# RATT_REV0.net
KiCad netlist of a schematic drawn in EAGLE
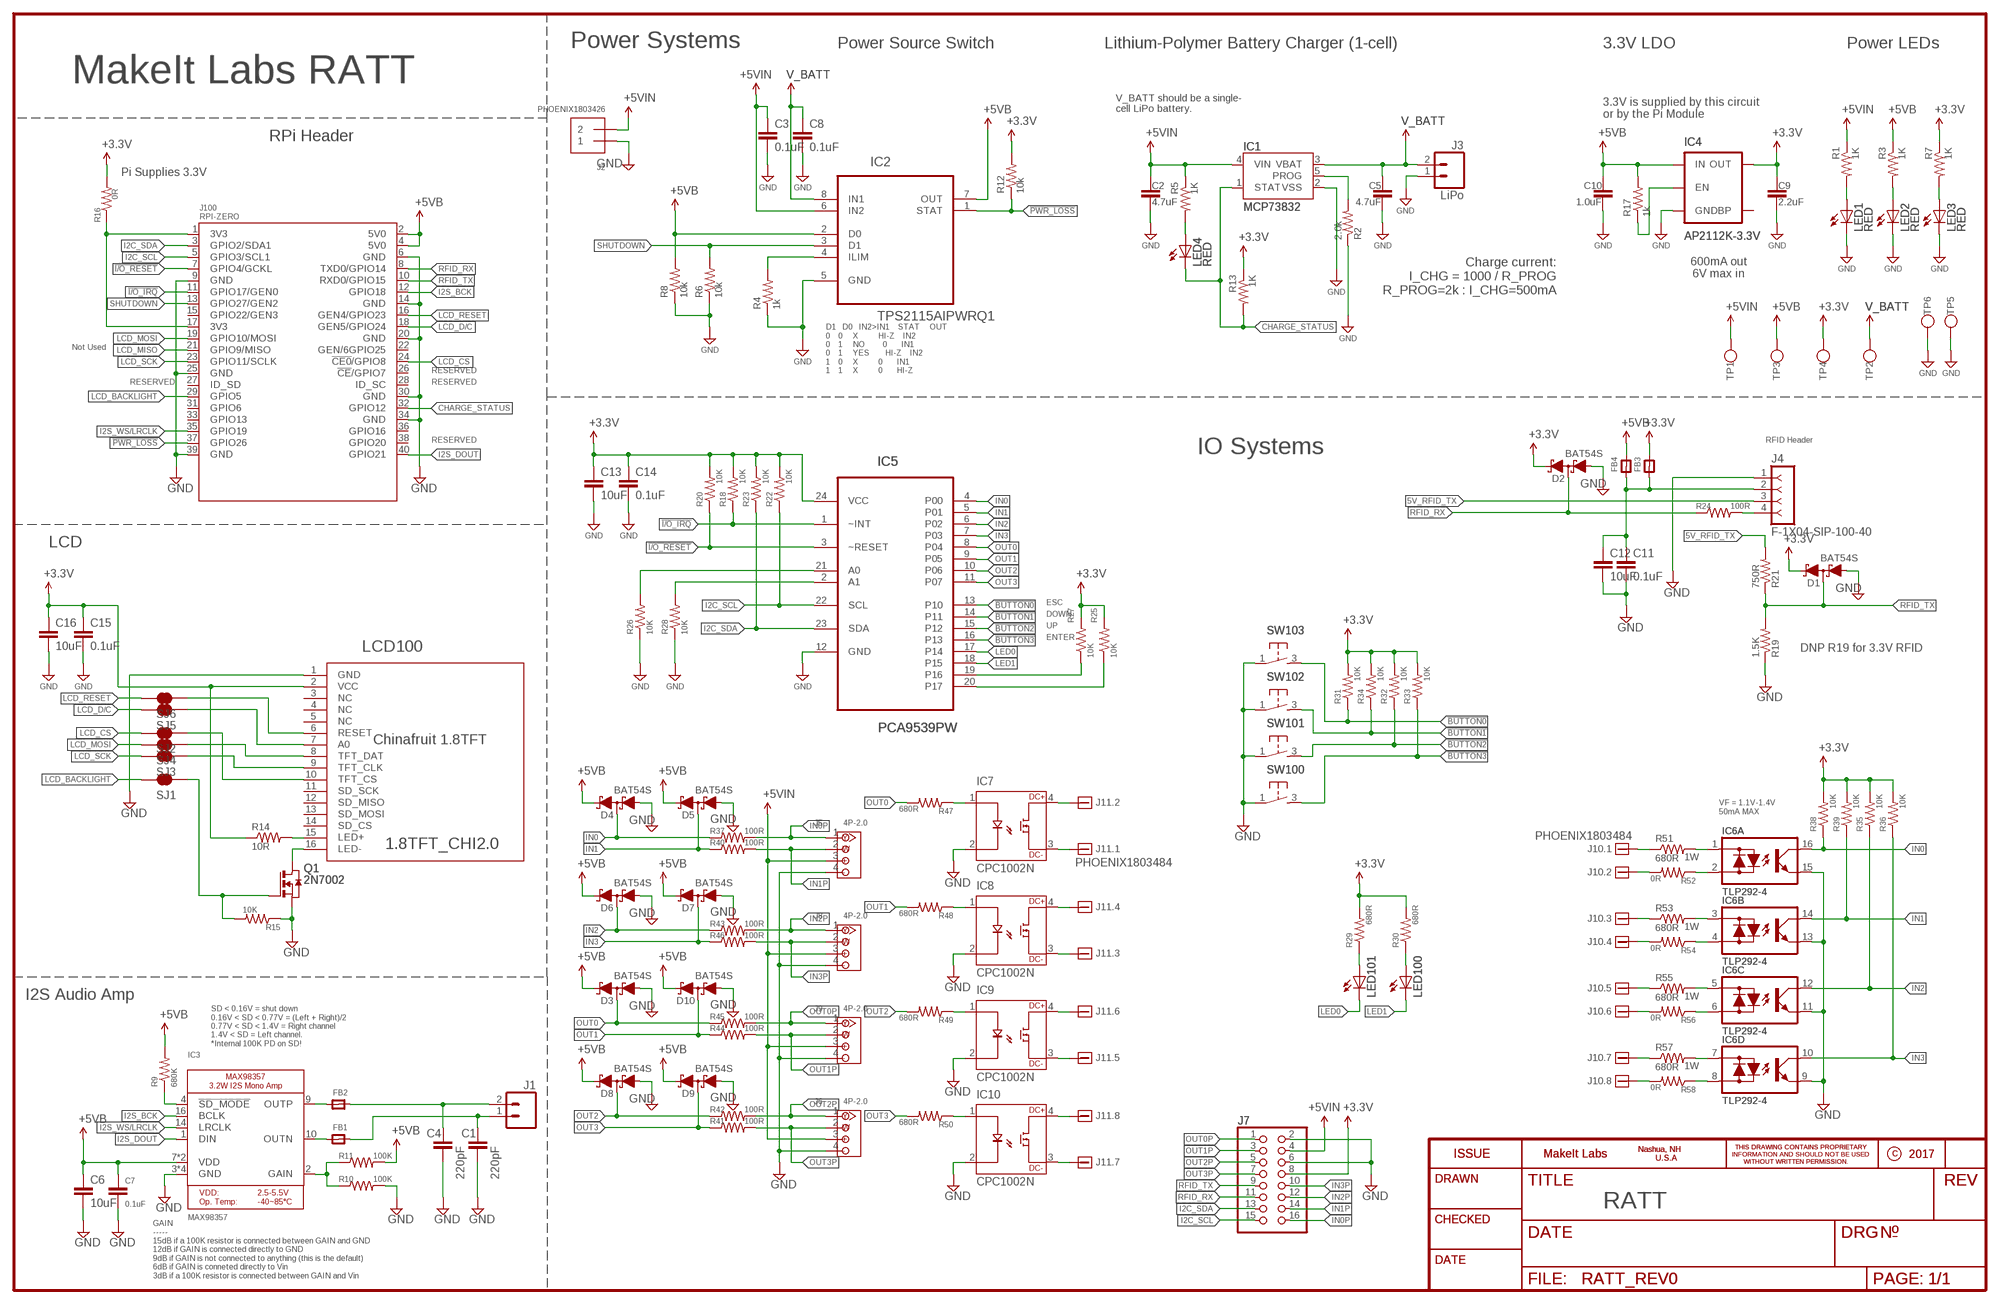
[diagram p0: schematic, sheet 1]

(export (version "E")
  (design (tool "Eeschema 10.0.6"))
  (components
    (comp (ref "C1")
      (value "220pF")
      (footprint "eagle-import:0603-CAP")
      (libsource (lib "eagle-import") (part "CAP0603"))
    )
    (comp (ref "C2")
      (value "4.7uF")
      (footprint "eagle-import:0603-CAP")
      (libsource (lib "eagle-import") (part "CAP0603"))
    )
    (comp (ref "C3")
      (value "0.1uF")
      (footprint "eagle-import:0603-CAP")
      (libsource (lib "eagle-import") (part "CAP0603"))
    )
    (comp (ref "C4")
      (value "220pF")
      (footprint "eagle-import:0603-CAP")
      (libsource (lib "eagle-import") (part "CAP0603"))
    )
    (comp (ref "C5")
      (value "4.7uF")
      (footprint "eagle-import:0603-CAP")
      (libsource (lib "eagle-import") (part "CAP0603"))
    )
    (comp (ref "C6")
      (value "10uF")
      (footprint "eagle-import:0805-CAP")
      (libsource (lib "eagle-import") (part "CAP0805"))
    )
    (comp (ref "C7")
      (value "0.1uF")
      (footprint "eagle-import:0603-CAP")
      (libsource (lib "eagle-import") (part "CAP0603"))
    )
    (comp (ref "C8")
      (value "0.1uF")
      (footprint "eagle-import:0603-CAP")
      (libsource (lib "eagle-import") (part "CAP0603"))
    )
    (comp (ref "C9")
      (value "2.2uF")
      (footprint "eagle-import:0603-CAP")
      (libsource (lib "eagle-import") (part "CAP0603"))
    )
    (comp (ref "C10")
      (value "1.0uF")
      (footprint "eagle-import:0603-CAP")
      (libsource (lib "eagle-import") (part "CAP0603"))
    )
    (comp (ref "C11")
      (value "0.1uF")
      (footprint "eagle-import:0603-CAP")
      (libsource (lib "eagle-import") (part "CAP0603"))
    )
    (comp (ref "C12")
      (value "10uF")
      (footprint "eagle-import:0805-CAP")
      (libsource (lib "eagle-import") (part "CAP0805"))
    )
    (comp (ref "C13")
      (value "10uF")
      (footprint "eagle-import:0805-CAP")
      (libsource (lib "eagle-import") (part "CAP0805"))
    )
    (comp (ref "C14")
      (value "0.1uF")
      (footprint "eagle-import:0603-CAP")
      (libsource (lib "eagle-import") (part "CAP0603"))
    )
    (comp (ref "C15")
      (value "0.1uF")
      (footprint "eagle-import:0603-CAP")
      (libsource (lib "eagle-import") (part "CAP0603"))
    )
    (comp (ref "C16")
      (value "10uF")
      (footprint "eagle-import:0805-CAP")
      (libsource (lib "eagle-import") (part "CAP0805"))
    )
    (comp (ref "D1")
      (value "BAT54S")
      (footprint "eagle-import:SOT-23")
      (libsource (lib "eagle-import") (part "BAT54S"))
    )
    (comp (ref "D2")
      (value "BAT54S")
      (footprint "eagle-import:SOT-23")
      (libsource (lib "eagle-import") (part "BAT54S"))
    )
    (comp (ref "D3")
      (value "BAT54S")
      (footprint "eagle-import:SOT-23")
      (libsource (lib "eagle-import") (part "BAT54S"))
    )
    (comp (ref "D4")
      (value "BAT54S")
      (footprint "eagle-import:SOT-23")
      (libsource (lib "eagle-import") (part "BAT54S"))
    )
    (comp (ref "D5")
      (value "BAT54S")
      (footprint "eagle-import:SOT-23")
      (libsource (lib "eagle-import") (part "BAT54S"))
    )
    (comp (ref "D6")
      (value "BAT54S")
      (footprint "eagle-import:SOT-23")
      (libsource (lib "eagle-import") (part "BAT54S"))
    )
    (comp (ref "D7")
      (value "BAT54S")
      (footprint "eagle-import:SOT-23")
      (libsource (lib "eagle-import") (part "BAT54S"))
    )
    (comp (ref "D8")
      (value "BAT54S")
      (footprint "eagle-import:SOT-23")
      (libsource (lib "eagle-import") (part "BAT54S"))
    )
    (comp (ref "D9")
      (value "BAT54S")
      (footprint "eagle-import:SOT-23")
      (libsource (lib "eagle-import") (part "BAT54S"))
    )
    (comp (ref "D10")
      (value "BAT54S")
      (footprint "eagle-import:SOT-23")
      (libsource (lib "eagle-import") (part "BAT54S"))
    )
    (comp (ref "FB1")
      (value "FERRITE")
      (footprint "eagle-import:0603")
      (libsource (lib "eagle-import") (part "FERRITE"))
    )
    (comp (ref "FB2")
      (value "FERRITE")
      (footprint "eagle-import:0603")
      (libsource (lib "eagle-import") (part "FERRITE"))
    )
    (comp (ref "FB3")
      (value "FERRITE")
      (footprint "eagle-import:0603")
      (libsource (lib "eagle-import") (part "FERRITE"))
    )
    (comp (ref "FB4")
      (value "FERRITE")
      (footprint "eagle-import:0603")
      (libsource (lib "eagle-import") (part "FERRITE"))
    )
    (comp (ref "IC1")
      (value "MCP73832")
      (footprint "eagle-import:SOT23-5")
      (libsource (lib "eagle-import") (part "MCP73831"))
    )
    (comp (ref "IC2")
      (value "TPS2115AIPWRQ1")
      (footprint "eagle-import:SOP65P640X120-8N")
      (libsource (lib "eagle-import") (part "TPS2115AIPWRQ1"))
    )
    (comp (ref "IC3")
      (value "MAX98357")
      (footprint "eagle-import:QFN16_3MM")
      (libsource (lib "eagle-import") (part "AUDIOAMP_MAX98357"))
    )
    (comp (ref "IC4")
      (value "AP2112K-3.3V")
      (footprint "eagle-import:SOT23-5")
      (libsource (lib "eagle-import") (part "V_REG_LDOSMD"))
    )
    (comp (ref "IC5")
      (value "PCA9539PW")
      (footprint "eagle-import:SOP65P640X120-24N")
      (libsource (lib "eagle-import") (part "PCA9539PW"))
    )
    (comp (ref "IC6")
      (value "TLP292-4")
      (footprint "eagle-import:SO-16")
      (libsource (lib "eagle-import") (part "TLP292-4"))
    )
    (comp (ref "IC7")
      (value "CPC1002N")
      (footprint "eagle-import:CPC1002N")
      (libsource (lib "eagle-import") (part "CPC1002N"))
    )
    (comp (ref "IC8")
      (value "CPC1002N")
      (footprint "eagle-import:CPC1002N")
      (libsource (lib "eagle-import") (part "CPC1002N"))
    )
    (comp (ref "IC9")
      (value "CPC1002N")
      (footprint "eagle-import:CPC1002N")
      (libsource (lib "eagle-import") (part "CPC1002N"))
    )
    (comp (ref "IC10")
      (value "CPC1002N")
      (footprint "eagle-import:CPC1002N")
      (libsource (lib "eagle-import") (part "CPC1002N"))
    )
    (comp (ref "J1")
      (value "M02POLAR")
      (footprint "eagle-import:MOLEX-1X2")
      (libsource (lib "eagle-import") (part "M02POLAR"))
    )
    (comp (ref "J2")
      (value "PHOENIX1803426")
      (footprint "eagle-import:1803426")
      (libsource (lib "eagle-import") (part "PHOENIX1803426"))
    )
    (comp (ref "J3")
      (value "LiPo")
      (footprint "eagle-import:JST-2-PTH")
      (libsource (lib "eagle-import") (part "M02JST-PTH-2"))
    )
    (comp (ref "J4")
      (value "F-1X04-SIP-100-40")
      (footprint "eagle-import:SIP-100-04-40")
      (libsource (lib "eagle-import") (part "F-1X04-SIP-100-40"))
    )
    (comp (ref "J5")
      (value "4P-2.0")
      (footprint "eagle-import:HW4-2.0")
      (libsource (lib "eagle-import") (part "GROVE-CONNECTOR-TH-VERT"))
    )
    (comp (ref "J6")
      (value "4P-2.0")
      (footprint "eagle-import:HW4-2.0")
      (libsource (lib "eagle-import") (part "GROVE-CONNECTOR-TH-VERT"))
    )
    (comp (ref "J7")
      (value "PINHD-2X8SHROUD")
      (footprint "eagle-import:2X08_SHROUD")
      (libsource (lib "eagle-import") (part "PINHD-2X8SHROUD"))
    )
    (comp (ref "J8")
      (value "4P-2.0")
      (footprint "eagle-import:HW4-2.0")
      (libsource (lib "eagle-import") (part "GROVE-CONNECTOR-TH-VERT"))
    )
    (comp (ref "J9")
      (value "4P-2.0")
      (footprint "eagle-import:HW4-2.0")
      (libsource (lib "eagle-import") (part "GROVE-CONNECTOR-TH-VERT"))
    )
    (comp (ref "J10")
      (value "PHOENIX1803484")
      (footprint "eagle-import:1803484")
      (libsource (lib "eagle-import") (part "PHOENIX1803484"))
    )
    (comp (ref "J11")
      (value "PHOENIX1803484")
      (footprint "eagle-import:1803484")
      (libsource (lib "eagle-import") (part "PHOENIX1803484"))
    )
    (comp (ref "J100")
      (value "RPI-ZERO")
      (footprint "eagle-import:RASPBERRYPI_BASTELSTUBE_V13_RASPI_BOARD_B+_FULL")
      (libsource (lib "eagle-import") (part "RPI-ZERO"))
    )
    (comp (ref "LCD100")
      (value "1.8TFT_CHI2.0")
      (footprint "eagle-import:1.8TFT_CHI_2.0")
      (libsource (lib "eagle-import") (part "1.8TFT_CHI2.0"))
    )
    (comp (ref "LED1")
      (value "RED")
      (footprint "eagle-import:LED-0603")
      (libsource (lib "eagle-import") (part "LED-RED0603"))
    )
    (comp (ref "LED2")
      (value "RED")
      (footprint "eagle-import:LED-0603")
      (libsource (lib "eagle-import") (part "LED-RED0603"))
    )
    (comp (ref "LED3")
      (value "RED")
      (footprint "eagle-import:LED-0603")
      (libsource (lib "eagle-import") (part "LED-RED0603"))
    )
    (comp (ref "LED4")
      (value "RED")
      (footprint "eagle-import:LED-0603")
      (libsource (lib "eagle-import") (part "LED-RED0603"))
    )
    (comp (ref "LED100")
      (value "LED5MM")
      (footprint "eagle-import:LED5MM")
      (libsource (lib "eagle-import") (part "LED5MM"))
    )
    (comp (ref "LED101")
      (value "LED5MM")
      (footprint "eagle-import:LED5MM")
      (libsource (lib "eagle-import") (part "LED5MM"))
    )
    (comp (ref "Q1")
      (value "2N7002")
      (footprint "eagle-import:SOT-23")
      (libsource (lib "eagle-import") (part "NMOSSOT23"))
    )
    (comp (ref "R1")
      (value "1K")
      (footprint "eagle-import:0603-RES")
      (libsource (lib "eagle-import") (part "RESISTOR0603"))
    )
    (comp (ref "R2")
      (value "2.0k")
      (footprint "eagle-import:0603-RES")
      (libsource (lib "eagle-import") (part "RESISTOR0603"))
    )
    (comp (ref "R3")
      (value "1K")
      (footprint "eagle-import:0603-RES")
      (libsource (lib "eagle-import") (part "RESISTOR0603"))
    )
    (comp (ref "R4")
      (value "1k")
      (footprint "eagle-import:0603-RES")
      (libsource (lib "eagle-import") (part "RESISTOR0603"))
    )
    (comp (ref "R5")
      (value "1K")
      (footprint "eagle-import:0603-RES")
      (libsource (lib "eagle-import") (part "RESISTOR0603"))
    )
    (comp (ref "R6")
      (value "10k")
      (footprint "eagle-import:0603-RES")
      (libsource (lib "eagle-import") (part "RESISTOR0603"))
    )
    (comp (ref "R7")
      (value "1K")
      (footprint "eagle-import:0603-RES")
      (libsource (lib "eagle-import") (part "RESISTOR0603"))
    )
    (comp (ref "R8")
      (value "10k")
      (footprint "eagle-import:0603-RES")
      (libsource (lib "eagle-import") (part "RESISTOR0603"))
    )
    (comp (ref "R9")
      (value "680K")
      (footprint "eagle-import:0603-RES")
      (libsource (lib "eagle-import") (part "RESISTOR0603"))
    )
    (comp (ref "R10")
      (value "100K")
      (footprint "eagle-import:0603-RES")
      (libsource (lib "eagle-import") (part "RESISTOR0603"))
    )
    (comp (ref "R11")
      (value "100K")
      (footprint "eagle-import:0603-RES")
      (libsource (lib "eagle-import") (part "RESISTOR0603"))
    )
    (comp (ref "R12")
      (value "10k")
      (footprint "eagle-import:0603-RES")
      (libsource (lib "eagle-import") (part "RESISTOR0603"))
    )
    (comp (ref "R13")
      (value "1K")
      (footprint "eagle-import:0603-RES")
      (libsource (lib "eagle-import") (part "RESISTOR0603"))
    )
    (comp (ref "R14")
      (value "10R")
      (footprint "eagle-import:1206-RES")
      (libsource (lib "eagle-import") (part "RESISTOR1206"))
    )
    (comp (ref "R15")
      (value "10K")
      (footprint "eagle-import:0603-RES")
      (libsource (lib "eagle-import") (part "RESISTOR0603"))
    )
    (comp (ref "R16")
      (value "0R")
      (footprint "eagle-import:0603-RES")
      (libsource (lib "eagle-import") (part "RESISTOR0603"))
    )
    (comp (ref "R17")
      (value "1k")
      (footprint "eagle-import:0603-RES")
      (libsource (lib "eagle-import") (part "RESISTOR0603"))
    )
    (comp (ref "R18")
      (value "10K")
      (footprint "eagle-import:0603-RES")
      (libsource (lib "eagle-import") (part "RESISTOR0603"))
    )
    (comp (ref "R19")
      (value "1.5K")
      (footprint "eagle-import:0603-RES")
      (libsource (lib "eagle-import") (part "RESISTOR0603"))
    )
    (comp (ref "R20")
      (value "10K")
      (footprint "eagle-import:0603-RES")
      (libsource (lib "eagle-import") (part "RESISTOR0603"))
    )
    (comp (ref "R21")
      (value "750R")
      (footprint "eagle-import:0603-RES")
      (libsource (lib "eagle-import") (part "RESISTOR0603"))
    )
    (comp (ref "R22")
      (value "10K")
      (footprint "eagle-import:0603-RES")
      (libsource (lib "eagle-import") (part "RESISTOR0603"))
    )
    (comp (ref "R23")
      (value "10K")
      (footprint "eagle-import:0603-RES")
      (libsource (lib "eagle-import") (part "RESISTOR0603"))
    )
    (comp (ref "R24")
      (value "100R")
      (footprint "eagle-import:0603-RES")
      (libsource (lib "eagle-import") (part "RESISTOR0603"))
    )
    (comp (ref "R25")
      (value "10K")
      (footprint "eagle-import:0603-RES")
      (libsource (lib "eagle-import") (part "RESISTOR0603"))
    )
    (comp (ref "R26")
      (value "10K")
      (footprint "eagle-import:0603-RES")
      (libsource (lib "eagle-import") (part "RESISTOR0603"))
    )
    (comp (ref "R27")
      (value "10K")
      (footprint "eagle-import:0603-RES")
      (libsource (lib "eagle-import") (part "RESISTOR0603"))
    )
    (comp (ref "R28")
      (value "10K")
      (footprint "eagle-import:0603-RES")
      (libsource (lib "eagle-import") (part "RESISTOR0603"))
    )
    (comp (ref "R29")
      (value "680R")
      (footprint "eagle-import:0603-RES")
      (libsource (lib "eagle-import") (part "RESISTOR0603"))
    )
    (comp (ref "R30")
      (value "680R")
      (footprint "eagle-import:0603-RES")
      (libsource (lib "eagle-import") (part "RESISTOR0603"))
    )
    (comp (ref "R31")
      (value "10K")
      (footprint "eagle-import:0603-RES")
      (libsource (lib "eagle-import") (part "RESISTOR0603"))
    )
    (comp (ref "R32")
      (value "10K")
      (footprint "eagle-import:0603-RES")
      (libsource (lib "eagle-import") (part "RESISTOR0603"))
    )
    (comp (ref "R33")
      (value "10K")
      (footprint "eagle-import:0603-RES")
      (libsource (lib "eagle-import") (part "RESISTOR0603"))
    )
    (comp (ref "R34")
      (value "10K")
      (footprint "eagle-import:0603-RES")
      (libsource (lib "eagle-import") (part "RESISTOR0603"))
    )
    (comp (ref "R35")
      (value "10K")
      (footprint "eagle-import:0603-RES")
      (libsource (lib "eagle-import") (part "RESISTOR0603"))
    )
    (comp (ref "R36")
      (value "10K")
      (footprint "eagle-import:0603-RES")
      (libsource (lib "eagle-import") (part "RESISTOR0603"))
    )
    (comp (ref "R37")
      (value "100R")
      (footprint "eagle-import:0603-RES")
      (libsource (lib "eagle-import") (part "RESISTOR0603"))
    )
    (comp (ref "R38")
      (value "10K")
      (footprint "eagle-import:0603-RES")
      (libsource (lib "eagle-import") (part "RESISTOR0603"))
    )
    (comp (ref "R39")
      (value "10K")
      (footprint "eagle-import:0603-RES")
      (libsource (lib "eagle-import") (part "RESISTOR0603"))
    )
    (comp (ref "R40")
      (value "100R")
      (footprint "eagle-import:0603-RES")
      (libsource (lib "eagle-import") (part "RESISTOR0603"))
    )
    (comp (ref "R41")
      (value "100R")
      (footprint "eagle-import:0603-RES")
      (libsource (lib "eagle-import") (part "RESISTOR0603"))
    )
    (comp (ref "R42")
      (value "100R")
      (footprint "eagle-import:0603-RES")
      (libsource (lib "eagle-import") (part "RESISTOR0603"))
    )
    (comp (ref "R43")
      (value "100R")
      (footprint "eagle-import:0603-RES")
      (libsource (lib "eagle-import") (part "RESISTOR0603"))
    )
    (comp (ref "R44")
      (value "100R")
      (footprint "eagle-import:0603-RES")
      (libsource (lib "eagle-import") (part "RESISTOR0603"))
    )
    (comp (ref "R45")
      (value "100R")
      (footprint "eagle-import:0603-RES")
      (libsource (lib "eagle-import") (part "RESISTOR0603"))
    )
    (comp (ref "R46")
      (value "100R")
      (footprint "eagle-import:0603-RES")
      (libsource (lib "eagle-import") (part "RESISTOR0603"))
    )
    (comp (ref "R47")
      (value "680R")
      (footprint "eagle-import:0603-RES")
      (libsource (lib "eagle-import") (part "RESISTOR0603"))
    )
    (comp (ref "R48")
      (value "680R")
      (footprint "eagle-import:0603-RES")
      (libsource (lib "eagle-import") (part "RESISTOR0603"))
    )
    (comp (ref "R49")
      (value "680R")
      (footprint "eagle-import:0603-RES")
      (libsource (lib "eagle-import") (part "RESISTOR0603"))
    )
    (comp (ref "R50")
      (value "680R")
      (footprint "eagle-import:0603-RES")
      (libsource (lib "eagle-import") (part "RESISTOR0603"))
    )
    (comp (ref "R51")
      (value "680R")
      (footprint "eagle-import:2512-RES")
      (fields (field (name "P") "1W"))
      (libsource (lib "eagle-import") (part "RESISTOR2512"))
    )
    (comp (ref "R52")
      (value "0R")
      (footprint "eagle-import:0603-RES")
      (libsource (lib "eagle-import") (part "RESISTOR0603"))
    )
    (comp (ref "R53")
      (value "680R")
      (footprint "eagle-import:2512-RES")
      (fields (field (name "P") "1W"))
      (libsource (lib "eagle-import") (part "RESISTOR2512"))
    )
    (comp (ref "R54")
      (value "0R")
      (footprint "eagle-import:0603-RES")
      (libsource (lib "eagle-import") (part "RESISTOR0603"))
    )
    (comp (ref "R55")
      (value "680R")
      (footprint "eagle-import:2512-RES")
      (fields (field (name "P") "1W"))
      (libsource (lib "eagle-import") (part "RESISTOR2512"))
    )
    (comp (ref "R56")
      (value "0R")
      (footprint "eagle-import:0603-RES")
      (libsource (lib "eagle-import") (part "RESISTOR0603"))
    )
    (comp (ref "R57")
      (value "680R")
      (footprint "eagle-import:2512-RES")
      (fields (field (name "P") "1W"))
      (libsource (lib "eagle-import") (part "RESISTOR2512"))
    )
    (comp (ref "R58")
      (value "0R")
      (footprint "eagle-import:0603-RES")
      (libsource (lib "eagle-import") (part "RESISTOR0603"))
    )
    (comp (ref "SJ1")
      (value "JUMPER-PAD-2-NC_BY_TRACE")
      (footprint "eagle-import:SOLDERJUMPER_10MIL")
      (libsource (lib "eagle-import") (part "SOLDERJUMPER_CLOSED10MIL"))
    )
    (comp (ref "SJ2")
      (value "JUMPER-PAD-2-NC_BY_TRACE")
      (footprint "eagle-import:SOLDERJUMPER_10MIL")
      (libsource (lib "eagle-import") (part "SOLDERJUMPER_CLOSED10MIL"))
    )
    (comp (ref "SJ3")
      (value "JUMPER-PAD-2-NC_BY_TRACE")
      (footprint "eagle-import:SOLDERJUMPER_10MIL")
      (libsource (lib "eagle-import") (part "SOLDERJUMPER_CLOSED10MIL"))
    )
    (comp (ref "SJ4")
      (value "JUMPER-PAD-2-NC_BY_TRACE")
      (footprint "eagle-import:SOLDERJUMPER_10MIL")
      (libsource (lib "eagle-import") (part "SOLDERJUMPER_CLOSED10MIL"))
    )
    (comp (ref "SJ5")
      (value "JUMPER-PAD-2-NC_BY_TRACE")
      (footprint "eagle-import:SOLDERJUMPER_10MIL")
      (libsource (lib "eagle-import") (part "SOLDERJUMPER_CLOSED10MIL"))
    )
    (comp (ref "SJ6")
      (value "JUMPER-PAD-2-NC_BY_TRACE")
      (footprint "eagle-import:SOLDERJUMPER_10MIL")
      (libsource (lib "eagle-import") (part "SOLDERJUMPER_CLOSED10MIL"))
    )
    (comp (ref "SW100")
      (value "ESWITCH_320")
      (footprint "eagle-import:ESWITCH320")
      (libsource (lib "eagle-import") (part "ESWITCH_320"))
    )
    (comp (ref "SW101")
      (value "ESWITCH_320")
      (footprint "eagle-import:ESWITCH320")
      (libsource (lib "eagle-import") (part "ESWITCH_320"))
    )
    (comp (ref "SW102")
      (value "ESWITCH_320")
      (footprint "eagle-import:ESWITCH320")
      (libsource (lib "eagle-import") (part "ESWITCH_320"))
    )
    (comp (ref "SW103")
      (value "ESWITCH_320")
      (footprint "eagle-import:ESWITCH320")
      (libsource (lib "eagle-import") (part "ESWITCH_320"))
    )
    (comp (ref "TP1")
      (value "5VIN")
      (footprint "eagle-import:1206-RCW")
      (libsource (lib "eagle-import") (part "RCW-0C"))
    )
    (comp (ref "TP2")
      (value "BATT")
      (footprint "eagle-import:1206-RCW")
      (libsource (lib "eagle-import") (part "RCW-0C"))
    )
    (comp (ref "TP3")
      (value "5VB")
      (footprint "eagle-import:1206-RCW")
      (libsource (lib "eagle-import") (part "RCW-0C"))
    )
    (comp (ref "TP4")
      (value "3.3V")
      (footprint "eagle-import:1206-RCW")
      (libsource (lib "eagle-import") (part "RCW-0C"))
    )
    (comp (ref "TP5")
      (value "GND")
      (footprint "eagle-import:1206-RCW")
      (libsource (lib "eagle-import") (part "RCW-0C"))
    )
    (comp (ref "TP6")
      (value "GND")
      (footprint "eagle-import:1206-RCW")
      (libsource (lib "eagle-import") (part "RCW-0C"))
    )
  )
  (nets
    (net (code "1") (name "+3.3V") (class "Default")
      (node (ref "C13") (pin "1") (pinfunction "1_1") (pintype "passive"))
      (node (ref "C14") (pin "1") (pinfunction "1_1") (pintype "passive"))
      (node (ref "C15") (pin "1") (pinfunction "1_1") (pintype "passive"))
      (node (ref "C16") (pin "1") (pinfunction "1_1") (pintype "passive"))
      (node (ref "C9") (pin "1") (pinfunction "1_1") (pintype "passive"))
      (node (ref "D1") (pin "2") (pinfunction "C2_2") (pintype "passive"))
      (node (ref "D2") (pin "2") (pinfunction "C2_2") (pintype "passive"))
      (node (ref "FB3") (pin "2") (pinfunction "P$2_2") (pintype "passive"))
      (node (ref "IC4") (pin "5") (pinfunction "OUT_5") (pintype "passive"))
      (node (ref "IC5") (pin "24") (pinfunction "VCC_24") (pintype "power_in"))
      (node (ref "J7") (pin "8") (pinfunction "8_8") (pintype "passive"))
      (node (ref "LCD100") (pin "2") (pinfunction "VCC_2") (pintype "bidirectional"))
      (node (ref "R12") (pin "2") (pinfunction "2_2") (pintype "passive"))
      (node (ref "R13") (pin "1") (pinfunction "1_1") (pintype "passive"))
      (node (ref "R14") (pin "1") (pinfunction "1_1") (pintype "passive"))
      (node (ref "R16") (pin "2") (pinfunction "2_2") (pintype "passive"))
      (node (ref "R18") (pin "2") (pinfunction "2_2") (pintype "passive"))
      (node (ref "R20") (pin "2") (pinfunction "2_2") (pintype "passive"))
      (node (ref "R22") (pin "2") (pinfunction "2_2") (pintype "passive"))
      (node (ref "R23") (pin "2") (pinfunction "2_2") (pintype "passive"))
      (node (ref "R25") (pin "2") (pinfunction "2_2") (pintype "passive"))
      (node (ref "R27") (pin "2") (pinfunction "2_2") (pintype "passive"))
      (node (ref "R29") (pin "2") (pinfunction "2_2") (pintype "passive"))
      (node (ref "R30") (pin "2") (pinfunction "2_2") (pintype "passive"))
      (node (ref "R31") (pin "2") (pinfunction "2_2") (pintype "passive"))
      (node (ref "R32") (pin "2") (pinfunction "2_2") (pintype "passive"))
      (node (ref "R33") (pin "2") (pinfunction "2_2") (pintype "passive"))
      (node (ref "R34") (pin "2") (pinfunction "2_2") (pintype "passive"))
      (node (ref "R35") (pin "2") (pinfunction "2_2") (pintype "passive"))
      (node (ref "R36") (pin "2") (pinfunction "2_2") (pintype "passive"))
      (node (ref "R38") (pin "2") (pinfunction "2_2") (pintype "passive"))
      (node (ref "R39") (pin "2") (pinfunction "2_2") (pintype "passive"))
      (node (ref "R7") (pin "1") (pinfunction "1_1") (pintype "passive"))
      (node (ref "TP4") (pin "1") (pinfunction "TP_1") (pintype "bidirectional"))
    )
    (net (code "2") (name "+5VB") (class "Default")
      (node (ref "C10") (pin "1") (pinfunction "1_1") (pintype "passive"))
      (node (ref "C6") (pin "1") (pinfunction "1_1") (pintype "passive"))
      (node (ref "C7") (pin "1") (pinfunction "1_1") (pintype "passive"))
      (node (ref "D10") (pin "2") (pinfunction "C2_2") (pintype "passive"))
      (node (ref "D3") (pin "2") (pinfunction "C2_2") (pintype "passive"))
      (node (ref "D4") (pin "2") (pinfunction "C2_2") (pintype "passive"))
      (node (ref "D5") (pin "2") (pinfunction "C2_2") (pintype "passive"))
      (node (ref "D6") (pin "2") (pinfunction "C2_2") (pintype "passive"))
      (node (ref "D7") (pin "2") (pinfunction "C2_2") (pintype "passive"))
      (node (ref "D8") (pin "2") (pinfunction "C2_2") (pintype "passive"))
      (node (ref "D9") (pin "2") (pinfunction "C2_2") (pintype "passive"))
      (node (ref "FB4") (pin "2") (pinfunction "P$2_2") (pintype "passive"))
      (node (ref "IC2") (pin "2") (pinfunction "D0_2") (pintype "input"))
      (node (ref "IC2") (pin "7") (pinfunction "OUT_7") (pintype "output"))
      (node (ref "IC3") (pin "7") (pinfunction "VDD_7") (pintype "power_in"))
      (node (ref "IC3") (pin "8") (pinfunction "VDD_8") (pintype "power_in"))
      (node (ref "IC4") (pin "1") (pinfunction "IN_1") (pintype "input"))
      (node (ref "J100") (pin "2") (pinfunction "5V0_2") (pintype "power_in"))
      (node (ref "J100") (pin "4") (pinfunction "5V0_4") (pintype "power_in"))
      (node (ref "R11") (pin "2") (pinfunction "2_2") (pintype "passive"))
      (node (ref "R17") (pin "2") (pinfunction "2_2") (pintype "passive"))
      (node (ref "R3") (pin "1") (pinfunction "1_1") (pintype "passive"))
      (node (ref "R8") (pin "2") (pinfunction "2_2") (pintype "passive"))
      (node (ref "R9") (pin "2") (pinfunction "2_2") (pintype "passive"))
      (node (ref "TP3") (pin "1") (pinfunction "TP_1") (pintype "bidirectional"))
    )
    (net (code "3") (name "+5VIN") (class "Default")
      (node (ref "C2") (pin "1") (pinfunction "1_1") (pintype "passive"))
      (node (ref "C3") (pin "1") (pinfunction "1_1") (pintype "passive"))
      (node (ref "IC1") (pin "4") (pinfunction "VIN_4") (pintype "power_in"))
      (node (ref "IC2") (pin "6") (pinfunction "IN2_6") (pintype "power_in"))
      (node (ref "J2") (pin "2") (pinfunction "2_2") (pintype "passive"))
      (node (ref "J5") (pin "3") (pinfunction "3_3") (pintype "bidirectional"))
      (node (ref "J6") (pin "3") (pinfunction "3_3") (pintype "bidirectional"))
      (node (ref "J7") (pin "4") (pinfunction "4_4") (pintype "passive"))
      (node (ref "J8") (pin "3") (pinfunction "3_3") (pintype "bidirectional"))
      (node (ref "J9") (pin "3") (pinfunction "3_3") (pintype "bidirectional"))
      (node (ref "R1") (pin "1") (pinfunction "1_1") (pintype "passive"))
      (node (ref "R5") (pin "1") (pinfunction "1_1") (pintype "passive"))
      (node (ref "TP1") (pin "1") (pinfunction "TP_1") (pintype "bidirectional"))
    )
    (net (code "4") (name "/GND") (class "Default")
      (node (ref "C1") (pin "2") (pinfunction "2_2") (pintype "passive"))
      (node (ref "C10") (pin "2") (pinfunction "2_2") (pintype "passive"))
      (node (ref "C11") (pin "2") (pinfunction "2_2") (pintype "passive"))
      (node (ref "C12") (pin "2") (pinfunction "2_2") (pintype "passive"))
      (node (ref "C13") (pin "2") (pinfunction "2_2") (pintype "passive"))
      (node (ref "C14") (pin "2") (pinfunction "2_2") (pintype "passive"))
      (node (ref "C15") (pin "2") (pinfunction "2_2") (pintype "passive"))
      (node (ref "C16") (pin "2") (pinfunction "2_2") (pintype "passive"))
      (node (ref "C2") (pin "2") (pinfunction "2_2") (pintype "passive"))
      (node (ref "C3") (pin "2") (pinfunction "2_2") (pintype "passive"))
      (node (ref "C4") (pin "2") (pinfunction "2_2") (pintype "passive"))
      (node (ref "C5") (pin "2") (pinfunction "2_2") (pintype "passive"))
      (node (ref "C6") (pin "2") (pinfunction "2_2") (pintype "passive"))
      (node (ref "C7") (pin "2") (pinfunction "2_2") (pintype "passive"))
      (node (ref "C8") (pin "2") (pinfunction "2_2") (pintype "passive"))
      (node (ref "C9") (pin "2") (pinfunction "2_2") (pintype "passive"))
      (node (ref "D1") (pin "1") (pinfunction "A1_1") (pintype "passive"))
      (node (ref "D10") (pin "1") (pinfunction "A1_1") (pintype "passive"))
      (node (ref "D2") (pin "1") (pinfunction "A1_1") (pintype "passive"))
      (node (ref "D3") (pin "1") (pinfunction "A1_1") (pintype "passive"))
      (node (ref "D4") (pin "1") (pinfunction "A1_1") (pintype "passive"))
      (node (ref "D5") (pin "1") (pinfunction "A1_1") (pintype "passive"))
      (node (ref "D6") (pin "1") (pinfunction "A1_1") (pintype "passive"))
      (node (ref "D7") (pin "1") (pinfunction "A1_1") (pintype "passive"))
      (node (ref "D8") (pin "1") (pinfunction "A1_1") (pintype "passive"))
      (node (ref "D9") (pin "1") (pinfunction "A1_1") (pintype "passive"))
      (node (ref "IC1") (pin "2") (pinfunction "VSS_2") (pintype "power_in"))
      (node (ref "IC10") (pin "2") (pinfunction "CATHODE_2") (pintype "passive"))
      (node (ref "IC2") (pin "5") (pinfunction "GND_5") (pintype "passive"))
      (node (ref "IC3") (pin "11") (pinfunction "GND_11") (pintype "power_in"))
      (node (ref "IC3") (pin "15") (pinfunction "GND_15") (pintype "power_in"))
      (node (ref "IC3") (pin "3") (pinfunction "GND_3") (pintype "power_in"))
      (node (ref "IC3") (pin "THERMAL") (pinfunction "GND_THERMAL") (pintype "power_in"))
      (node (ref "IC4") (pin "2") (pinfunction "GND_2") (pintype "input"))
      (node (ref "IC5") (pin "12") (pinfunction "GND_12") (pintype "passive"))
      (node (ref "IC6") (pin "11") (pinfunction "E_11") (pintype "passive"))
      (node (ref "IC6") (pin "13") (pinfunction "E_13") (pintype "passive"))
      (node (ref "IC6") (pin "15") (pinfunction "E_15") (pintype "passive"))
      (node (ref "IC6") (pin "9") (pinfunction "E_9") (pintype "passive"))
      (node (ref "IC7") (pin "2") (pinfunction "CATHODE_2") (pintype "passive"))
      (node (ref "IC8") (pin "2") (pinfunction "CATHODE_2") (pintype "passive"))
      (node (ref "IC9") (pin "2") (pinfunction "CATHODE_2") (pintype "passive"))
      (node (ref "J100") (pin "14") (pinfunction "GND_14") (pintype "power_in"))
      (node (ref "J100") (pin "20") (pinfunction "GND_20") (pintype "power_in"))
      (node (ref "J100") (pin "25") (pinfunction "GND_25") (pintype "power_in"))
      (node (ref "J100") (pin "30") (pinfunction "GND_30") (pintype "power_in"))
      (node (ref "J100") (pin "34") (pinfunction "GND_34") (pintype "power_in"))
      (node (ref "J100") (pin "39") (pinfunction "GND_39") (pintype "power_in"))
      (node (ref "J100") (pin "6") (pinfunction "GND_6") (pintype "power_in"))
      (node (ref "J100") (pin "9") (pinfunction "GND_9") (pintype "power_in"))
      (node (ref "J2") (pin "1") (pinfunction "1_1") (pintype "passive"))
      (node (ref "J3") (pin "1") (pinfunction "1_1") (pintype "passive"))
      (node (ref "J4") (pin "1") (pinfunction "1_1") (pintype "passive"))
      (node (ref "J5") (pin "4") (pinfunction "4_4") (pintype "bidirectional"))
      (node (ref "J6") (pin "4") (pinfunction "4_4") (pintype "bidirectional"))
      (node (ref "J7") (pin "2") (pinfunction "2_2") (pintype "passive"))
      (node (ref "J7") (pin "6") (pinfunction "6_6") (pintype "passive"))
      (node (ref "J8") (pin "4") (pinfunction "4_4") (pintype "bidirectional"))
      (node (ref "J9") (pin "4") (pinfunction "4_4") (pintype "bidirectional"))
      (node (ref "LCD100") (pin "1") (pinfunction "GND_1") (pintype "bidirectional"))
      (node (ref "LED1") (pin "C") (pinfunction "C_C") (pintype "passive"))
      (node (ref "LED2") (pin "C") (pinfunction "C_C") (pintype "passive"))
      (node (ref "LED3") (pin "C") (pinfunction "C_C") (pintype "passive"))
      (node (ref "Q1") (pin "2") (pinfunction "S_2") (pintype "passive"))
      (node (ref "R10") (pin "2") (pinfunction "2_2") (pintype "passive"))
      (node (ref "R15") (pin "1") (pinfunction "1_1") (pintype "passive"))
      (node (ref "R19") (pin "1") (pinfunction "1_1") (pintype "passive"))
      (node (ref "R2") (pin "1") (pinfunction "1_1") (pintype "passive"))
      (node (ref "R26") (pin "1") (pinfunction "1_1") (pintype "passive"))
      (node (ref "R28") (pin "1") (pinfunction "1_1") (pintype "passive"))
      (node (ref "R4") (pin "1") (pinfunction "1_1") (pintype "passive"))
      (node (ref "R6") (pin "1") (pinfunction "1_1") (pintype "passive"))
      (node (ref "R8") (pin "1") (pinfunction "1_1") (pintype "passive"))
      (node (ref "SW100") (pin "1") (pinfunction "1_1") (pintype "passive"))
      (node (ref "SW101") (pin "1") (pinfunction "1_1") (pintype "passive"))
      (node (ref "SW102") (pin "1") (pinfunction "1_1") (pintype "passive"))
      (node (ref "SW103") (pin "1") (pinfunction "1_1") (pintype "passive"))
      (node (ref "TP5") (pin "1") (pinfunction "TP_1") (pintype "bidirectional"))
      (node (ref "TP6") (pin "1") (pinfunction "TP_1") (pintype "bidirectional"))
    )
    (net (code "5") (name "/V_BATT") (class "Default")
      (node (ref "C5") (pin "1") (pinfunction "1_1") (pintype "passive"))
      (node (ref "C8") (pin "1") (pinfunction "1_1") (pintype "passive"))
      (node (ref "IC1") (pin "3") (pinfunction "VBAT_3") (pintype "power_in"))
      (node (ref "IC2") (pin "8") (pinfunction "IN1_8") (pintype "power_in"))
      (node (ref "J3") (pin "2") (pinfunction "2_2") (pintype "passive"))
      (node (ref "TP2") (pin "1") (pinfunction "TP_1") (pintype "bidirectional"))
    )
    (net (code "6") (name "/~{BUTTON0}") (class "Default")
      (node (ref "IC5") (pin "13") (pinfunction "P10_13") (pintype "bidirectional"))
      (node (ref "R31") (pin "1") (pinfunction "1_1") (pintype "passive"))
      (node (ref "SW103") (pin "3") (pinfunction "3_3") (pintype "passive"))
    )
    (net (code "7") (name "/~{BUTTON1}") (class "Default")
      (node (ref "IC5") (pin "14") (pinfunction "P11_14") (pintype "bidirectional"))
      (node (ref "R34") (pin "1") (pinfunction "1_1") (pintype "passive"))
      (node (ref "SW102") (pin "3") (pinfunction "3_3") (pintype "passive"))
    )
    (net (code "8") (name "/~{BUTTON2}") (class "Default")
      (node (ref "IC5") (pin "15") (pinfunction "P12_15") (pintype "bidirectional"))
      (node (ref "R32") (pin "1") (pinfunction "1_1") (pintype "passive"))
      (node (ref "SW101") (pin "3") (pinfunction "3_3") (pintype "passive"))
    )
    (net (code "9") (name "/~{BUTTON3}") (class "Default")
      (node (ref "IC5") (pin "16") (pinfunction "P13_16") (pintype "bidirectional"))
      (node (ref "R33") (pin "1") (pinfunction "1_1") (pintype "passive"))
      (node (ref "SW100") (pin "3") (pinfunction "3_3") (pintype "passive"))
    )
    (net (code "10") (name "/~{I{slash}O_IRQ}") (class "Default")
      (node (ref "IC5") (pin "1") (pinfunction "~{INT}_1") (pintype "output"))
      (node (ref "J100") (pin "11") (pinfunction "GPIO17/GEN0_11") (pintype "bidirectional"))
      (node (ref "R18") (pin "1") (pinfunction "1_1") (pintype "passive"))
    )
    (net (code "11") (name "/~{I{slash}O_RESET}") (class "Default")
      (node (ref "IC5") (pin "3") (pinfunction "~{RESET}_3") (pintype "input"))
      (node (ref "J100") (pin "7") (pinfunction "GPIO4/GCKL_7") (pintype "bidirectional"))
      (node (ref "R20") (pin "1") (pinfunction "1_1") (pintype "passive"))
    )
    (net (code "12") (name "/~{PWR_LOSS}") (class "Default")
      (node (ref "IC2") (pin "1") (pinfunction "STAT_1") (pintype "output"))
      (node (ref "J100") (pin "37") (pinfunction "GPIO26_37") (pintype "bidirectional"))
      (node (ref "R12") (pin "1") (pinfunction "1_1") (pintype "passive"))
    )
    (net (code "13") (name "5V_RFID_TX") (class "Default")
      (node (ref "J4") (pin "3") (pinfunction "3_3") (pintype "passive"))
      (node (ref "R21") (pin "2") (pinfunction "2_2") (pintype "passive"))
    )
    (net (code "14") (name "CHARGE_STATUS") (class "Default")
      (node (ref "IC1") (pin "1") (pinfunction "STAT_1") (pintype "output"))
      (node (ref "J100") (pin "32") (pinfunction "GPIO12_32") (pintype "bidirectional"))
      (node (ref "LED4") (pin "C") (pinfunction "C_C") (pintype "passive"))
      (node (ref "R13") (pin "2") (pinfunction "2_2") (pintype "passive"))
    )
    (net (code "15") (name "I2C_SCL") (class "Default")
      (node (ref "IC5") (pin "22") (pinfunction "SCL_22") (pintype "input"))
      (node (ref "J100") (pin "5") (pinfunction "GPIO3/SCL1_5") (pintype "bidirectional"))
      (node (ref "J7") (pin "15") (pinfunction "15_15") (pintype "passive"))
      (node (ref "R22") (pin "1") (pinfunction "1_1") (pintype "passive"))
    )
    (net (code "16") (name "I2C_SDA") (class "Default")
      (node (ref "IC5") (pin "23") (pinfunction "SDA_23") (pintype "input"))
      (node (ref "J100") (pin "3") (pinfunction "GPIO2/SDA1_3") (pintype "bidirectional"))
      (node (ref "J7") (pin "13") (pinfunction "13_13") (pintype "passive"))
      (node (ref "R23") (pin "1") (pinfunction "1_1") (pintype "passive"))
    )
    (net (code "17") (name "I2S_BCK") (class "Default")
      (node (ref "IC3") (pin "16") (pinfunction "BCLK_16") (pintype "bidirectional"))
      (node (ref "J100") (pin "12") (pinfunction "GPIO18_12") (pintype "bidirectional"))
    )
    (net (code "18") (name "I2S_DOUT") (class "Default")
      (node (ref "IC3") (pin "1") (pinfunction "DIN_1") (pintype "bidirectional"))
      (node (ref "J100") (pin "40") (pinfunction "GPIO21_40") (pintype "bidirectional"))
    )
    (net (code "19") (name "I2S_WS{slash}LRCLK") (class "Default")
      (node (ref "IC3") (pin "14") (pinfunction "LRCLK_14") (pintype "bidirectional"))
      (node (ref "J100") (pin "35") (pinfunction "GPIO19_35") (pintype "bidirectional"))
    )
    (net (code "20") (name "IN0") (class "Default")
      (node (ref "D4") (pin "3") (pinfunction "C1A2_3") (pintype "passive"))
      (node (ref "IC5") (pin "4") (pinfunction "P00_4") (pintype "bidirectional"))
      (node (ref "IC6") (pin "16") (pinfunction "C_16") (pintype "passive"))
      (node (ref "R37") (pin "1") (pinfunction "1_1") (pintype "passive"))
      (node (ref "R38") (pin "1") (pinfunction "1_1") (pintype "passive"))
    )
    (net (code "21") (name "IN0P") (class "Default")
      (node (ref "J5") (pin "1") (pinfunction "1_1") (pintype "bidirectional"))
      (node (ref "J7") (pin "16") (pinfunction "16_16") (pintype "passive"))
      (node (ref "R37") (pin "2") (pinfunction "2_2") (pintype "passive"))
    )
    (net (code "22") (name "IN1") (class "Default")
      (node (ref "D5") (pin "3") (pinfunction "C1A2_3") (pintype "passive"))
      (node (ref "IC5") (pin "5") (pinfunction "P01_5") (pintype "bidirectional"))
      (node (ref "IC6") (pin "14") (pinfunction "C_14") (pintype "passive"))
      (node (ref "R39") (pin "1") (pinfunction "1_1") (pintype "passive"))
      (node (ref "R40") (pin "1") (pinfunction "1_1") (pintype "passive"))
    )
    (net (code "23") (name "IN1P") (class "Default")
      (node (ref "J5") (pin "2") (pinfunction "2_2") (pintype "bidirectional"))
      (node (ref "J7") (pin "14") (pinfunction "14_14") (pintype "passive"))
      (node (ref "R40") (pin "2") (pinfunction "2_2") (pintype "passive"))
    )
    (net (code "24") (name "IN2") (class "Default")
      (node (ref "D6") (pin "3") (pinfunction "C1A2_3") (pintype "passive"))
      (node (ref "IC5") (pin "6") (pinfunction "P02_6") (pintype "bidirectional"))
      (node (ref "IC6") (pin "12") (pinfunction "C_12") (pintype "passive"))
      (node (ref "R35") (pin "1") (pinfunction "1_1") (pintype "passive"))
      (node (ref "R43") (pin "1") (pinfunction "1_1") (pintype "passive"))
    )
    (net (code "25") (name "IN2P") (class "Default")
      (node (ref "J7") (pin "12") (pinfunction "12_12") (pintype "passive"))
      (node (ref "J8") (pin "1") (pinfunction "1_1") (pintype "bidirectional"))
      (node (ref "R43") (pin "2") (pinfunction "2_2") (pintype "passive"))
    )
    (net (code "26") (name "IN3") (class "Default")
      (node (ref "D7") (pin "3") (pinfunction "C1A2_3") (pintype "passive"))
      (node (ref "IC5") (pin "7") (pinfunction "P03_7") (pintype "bidirectional"))
      (node (ref "IC6") (pin "10") (pinfunction "C_10") (pintype "passive"))
      (node (ref "R36") (pin "1") (pinfunction "1_1") (pintype "passive"))
      (node (ref "R46") (pin "1") (pinfunction "1_1") (pintype "passive"))
    )
    (net (code "27") (name "IN3P") (class "Default")
      (node (ref "J7") (pin "10") (pinfunction "10_10") (pintype "passive"))
      (node (ref "J8") (pin "2") (pinfunction "2_2") (pintype "bidirectional"))
      (node (ref "R46") (pin "2") (pinfunction "2_2") (pintype "passive"))
    )
    (net (code "28") (name "LCD_BACKLIGHT") (class "Default")
      (node (ref "J100") (pin "29") (pinfunction "GPIO5_29") (pintype "bidirectional"))
      (node (ref "SJ1") (pin "2") (pinfunction "2_2") (pintype "passive"))
    )
    (net (code "29") (name "LCD_CS") (class "Default")
      (node (ref "J100") (pin "24") (pinfunction "~{CE0}/GPIO8_24") (pintype "bidirectional"))
      (node (ref "SJ2") (pin "2") (pinfunction "2_2") (pintype "passive"))
    )
    (net (code "30") (name "LCD_D{slash}C") (class "Default")
      (node (ref "J100") (pin "18") (pinfunction "GEN5/GPIO24_18") (pintype "bidirectional"))
      (node (ref "SJ5") (pin "2") (pinfunction "2_2") (pintype "passive"))
    )
    (net (code "31") (name "LCD_MISO") (class "Default")
      (node (ref "J100") (pin "21") (pinfunction "GPIO9/MISO_21") (pintype "bidirectional"))
    )
    (net (code "32") (name "LCD_MOSI") (class "Default")
      (node (ref "J100") (pin "19") (pinfunction "GPIO10/MOSI_19") (pintype "bidirectional"))
      (node (ref "SJ4") (pin "2") (pinfunction "2_2") (pintype "passive"))
    )
    (net (code "33") (name "LCD_RESET") (class "Default")
      (node (ref "J100") (pin "16") (pinfunction "GEN4/GPIO23_16") (pintype "bidirectional"))
      (node (ref "SJ6") (pin "2") (pinfunction "2_2") (pintype "passive"))
    )
    (net (code "34") (name "LCD_SCK") (class "Default")
      (node (ref "J100") (pin "23") (pinfunction "GPIO11/SCLK_23") (pintype "bidirectional"))
      (node (ref "SJ3") (pin "2") (pinfunction "2_2") (pintype "passive"))
    )
    (net (code "35") (name "LED0") (class "Default")
      (node (ref "IC5") (pin "17") (pinfunction "P14_17") (pintype "bidirectional"))
      (node (ref "LED101") (pin "K") (pinfunction "C_K") (pintype "passive"))
    )
    (net (code "36") (name "LED1") (class "Default")
      (node (ref "IC5") (pin "18") (pinfunction "P15_18") (pintype "bidirectional"))
      (node (ref "LED100") (pin "K") (pinfunction "C_K") (pintype "passive"))
    )
    (net (code "37") (name "Net-(FB1-P$1)") (class "Default")
      (node (ref "FB1") (pin "1") (pinfunction "P$1_1") (pintype "passive"))
      (node (ref "IC3") (pin "10") (pinfunction "OUTN_10") (pintype "output"))
    )
    (net (code "38") (name "Net-(FB1-P$2)") (class "Default")
      (node (ref "C1") (pin "1") (pinfunction "1_1") (pintype "passive"))
      (node (ref "FB1") (pin "2") (pinfunction "P$2_2") (pintype "passive"))
      (node (ref "J1") (pin "1") (pinfunction "1_1") (pintype "passive"))
    )
    (net (code "39") (name "Net-(FB2-P$1)") (class "Default")
      (node (ref "FB2") (pin "1") (pinfunction "P$1_1") (pintype "passive"))
      (node (ref "IC3") (pin "9") (pinfunction "OUTP_9") (pintype "output"))
    )
    (net (code "40") (name "Net-(FB2-P$2)") (class "Default")
      (node (ref "C4") (pin "1") (pinfunction "1_1") (pintype "passive"))
      (node (ref "FB2") (pin "2") (pinfunction "P$2_2") (pintype "passive"))
      (node (ref "J1") (pin "2") (pinfunction "2_2") (pintype "passive"))
    )
    (net (code "41") (name "Net-(FB3-P$1)") (class "Default")
      (node (ref "C11") (pin "1") (pinfunction "1_1") (pintype "passive"))
      (node (ref "C12") (pin "1") (pinfunction "1_1") (pintype "passive"))
      (node (ref "FB3") (pin "1") (pinfunction "P$1_1") (pintype "passive"))
      (node (ref "FB4") (pin "1") (pinfunction "P$1_1") (pintype "passive"))
      (node (ref "J4") (pin "2") (pinfunction "2_2") (pintype "passive"))
    )
    (net (code "42") (name "Net-(IC1-PROG)") (class "Default")
      (node (ref "IC1") (pin "5") (pinfunction "PROG_5") (pintype "input"))
      (node (ref "R2") (pin "2") (pinfunction "2_2") (pintype "passive"))
    )
    (net (code "43") (name "Net-(IC2-ILIM)") (class "Default")
      (node (ref "IC2") (pin "4") (pinfunction "ILIM_4") (pintype "input"))
      (node (ref "R4") (pin "2") (pinfunction "2_2") (pintype "passive"))
    )
    (net (code "44") (name "Net-(IC3-GAIN)") (class "Default")
      (node (ref "IC3") (pin "2") (pinfunction "GAIN_2") (pintype "bidirectional"))
      (node (ref "R10") (pin "1") (pinfunction "1_1") (pintype "passive"))
      (node (ref "R11") (pin "1") (pinfunction "1_1") (pintype "passive"))
    )
    (net (code "45") (name "Net-(IC3-~{SD_MODE})") (class "Default")
      (node (ref "IC3") (pin "4") (pinfunction "~{SD_MODE}_4") (pintype "bidirectional"))
      (node (ref "R9") (pin "1") (pinfunction "1_1") (pintype "passive"))
    )
    (net (code "46") (name "Net-(IC4-EN)") (class "Default")
      (node (ref "IC4") (pin "3") (pinfunction "EN_3") (pintype "input"))
      (node (ref "R17") (pin "1") (pinfunction "1_1") (pintype "passive"))
    )
    (net (code "47") (name "Net-(IC5-A0)") (class "Default")
      (node (ref "IC5") (pin "21") (pinfunction "A0_21") (pintype "bidirectional"))
      (node (ref "R26") (pin "2") (pinfunction "2_2") (pintype "passive"))
    )
    (net (code "48") (name "Net-(IC5-A1)") (class "Default")
      (node (ref "IC5") (pin "2") (pinfunction "A1_2") (pintype "input"))
      (node (ref "R28") (pin "2") (pinfunction "2_2") (pintype "passive"))
    )
    (net (code "49") (name "Net-(IC5-P16)") (class "Default")
      (node (ref "IC5") (pin "19") (pinfunction "P16_19") (pintype "bidirectional"))
      (node (ref "R27") (pin "1") (pinfunction "1_1") (pintype "passive"))
    )
    (net (code "50") (name "Net-(IC5-P17)") (class "Default")
      (node (ref "IC5") (pin "20") (pinfunction "P17_20") (pintype "bidirectional"))
      (node (ref "R25") (pin "1") (pinfunction "1_1") (pintype "passive"))
    )
    (net (code "51") (name "Net-(IC6A-AC1)") (class "Default")
      (node (ref "IC6") (pin "1") (pinfunction "AC1_1") (pintype "passive"))
      (node (ref "R51") (pin "2") (pinfunction "2_2") (pintype "passive"))
    )
    (net (code "52") (name "Net-(IC6A-AC2)") (class "Default")
      (node (ref "IC6") (pin "2") (pinfunction "AC2_2") (pintype "passive"))
      (node (ref "R52") (pin "1") (pinfunction "1_1") (pintype "passive"))
    )
    (net (code "53") (name "Net-(IC6B-AC1)") (class "Default")
      (node (ref "IC6") (pin "3") (pinfunction "AC1_3") (pintype "passive"))
      (node (ref "R53") (pin "2") (pinfunction "2_2") (pintype "passive"))
    )
    (net (code "54") (name "Net-(IC6B-AC2)") (class "Default")
      (node (ref "IC6") (pin "4") (pinfunction "AC2_4") (pintype "passive"))
      (node (ref "R54") (pin "1") (pinfunction "1_1") (pintype "passive"))
    )
    (net (code "55") (name "Net-(IC6C-AC1)") (class "Default")
      (node (ref "IC6") (pin "5") (pinfunction "AC1_5") (pintype "passive"))
      (node (ref "R55") (pin "2") (pinfunction "2_2") (pintype "passive"))
    )
    (net (code "56") (name "Net-(IC6C-AC2)") (class "Default")
      (node (ref "IC6") (pin "6") (pinfunction "AC2_6") (pintype "passive"))
      (node (ref "R56") (pin "1") (pinfunction "1_1") (pintype "passive"))
    )
    (net (code "57") (name "Net-(IC6D-AC1)") (class "Default")
      (node (ref "IC6") (pin "7") (pinfunction "AC1_7") (pintype "passive"))
      (node (ref "R57") (pin "2") (pinfunction "2_2") (pintype "passive"))
    )
    (net (code "58") (name "Net-(IC6D-AC2)") (class "Default")
      (node (ref "IC6") (pin "8") (pinfunction "AC2_8") (pintype "passive"))
      (node (ref "R58") (pin "1") (pinfunction "1_1") (pintype "passive"))
    )
    (net (code "59") (name "Net-(IC7-ANODE)") (class "Default")
      (node (ref "IC7") (pin "1") (pinfunction "ANODE_1") (pintype "passive"))
      (node (ref "R47") (pin "1") (pinfunction "1_1") (pintype "passive"))
    )
    (net (code "60") (name "Net-(IC7-DC+)") (class "Default")
      (node (ref "IC7") (pin "4") (pinfunction "DC+_4") (pintype "passive"))
      (node (ref "J11") (pin "2") (pinfunction "1_2") (pintype "passive"))
    )
    (net (code "61") (name "Net-(IC7-DC-)") (class "Default")
      (node (ref "IC7") (pin "3") (pinfunction "DC-_3") (pintype "passive"))
      (node (ref "J11") (pin "1") (pinfunction "1_1") (pintype "passive"))
    )
    (net (code "62") (name "Net-(IC8-ANODE)") (class "Default")
      (node (ref "IC8") (pin "1") (pinfunction "ANODE_1") (pintype "passive"))
      (node (ref "R48") (pin "1") (pinfunction "1_1") (pintype "passive"))
    )
    (net (code "63") (name "Net-(IC8-DC+)") (class "Default")
      (node (ref "IC8") (pin "4") (pinfunction "DC+_4") (pintype "passive"))
      (node (ref "J11") (pin "4") (pinfunction "1_4") (pintype "passive"))
    )
    (net (code "64") (name "Net-(IC8-DC-)") (class "Default")
      (node (ref "IC8") (pin "3") (pinfunction "DC-_3") (pintype "passive"))
      (node (ref "J11") (pin "3") (pinfunction "1_3") (pintype "passive"))
    )
    (net (code "65") (name "Net-(IC9-ANODE)") (class "Default")
      (node (ref "IC9") (pin "1") (pinfunction "ANODE_1") (pintype "passive"))
      (node (ref "R49") (pin "1") (pinfunction "1_1") (pintype "passive"))
    )
    (net (code "66") (name "Net-(IC9-DC+)") (class "Default")
      (node (ref "IC9") (pin "4") (pinfunction "DC+_4") (pintype "passive"))
      (node (ref "J11") (pin "6") (pinfunction "1_6") (pintype "passive"))
    )
    (net (code "67") (name "Net-(IC9-DC-)") (class "Default")
      (node (ref "IC9") (pin "3") (pinfunction "DC-_3") (pintype "passive"))
      (node (ref "J11") (pin "5") (pinfunction "1_5") (pintype "passive"))
    )
    (net (code "68") (name "Net-(IC10-ANODE)") (class "Default")
      (node (ref "IC10") (pin "1") (pinfunction "ANODE_1") (pintype "passive"))
      (node (ref "R50") (pin "1") (pinfunction "1_1") (pintype "passive"))
    )
    (net (code "69") (name "Net-(IC10-DC+)") (class "Default")
      (node (ref "IC10") (pin "4") (pinfunction "DC+_4") (pintype "passive"))
      (node (ref "J11") (pin "8") (pinfunction "1_8") (pintype "passive"))
    )
    (net (code "70") (name "Net-(IC10-DC-)") (class "Default")
      (node (ref "IC10") (pin "3") (pinfunction "DC-_3") (pintype "passive"))
      (node (ref "J11") (pin "7") (pinfunction "1_7") (pintype "passive"))
    )
    (net (code "71") (name "Net-(J4-Pad4)") (class "Default")
      (node (ref "J4") (pin "4") (pinfunction "4_4") (pintype "passive"))
      (node (ref "R24") (pin "2") (pinfunction "2_2") (pintype "passive"))
    )
    (net (code "72") (name "Net-(J10-Pad1)") (class "Default")
      (node (ref "J10") (pin "1") (pinfunction "1_1") (pintype "passive"))
      (node (ref "R51") (pin "1") (pinfunction "1_1") (pintype "passive"))
    )
    (net (code "73") (name "Net-(J10B-1)") (class "Default")
      (node (ref "J10") (pin "2") (pinfunction "1_2") (pintype "passive"))
      (node (ref "R52") (pin "2") (pinfunction "2_2") (pintype "passive"))
    )
    (net (code "74") (name "Net-(J10C-1)") (class "Default")
      (node (ref "J10") (pin "3") (pinfunction "1_3") (pintype "passive"))
      (node (ref "R53") (pin "1") (pinfunction "1_1") (pintype "passive"))
    )
    (net (code "75") (name "Net-(J10D-1)") (class "Default")
      (node (ref "J10") (pin "4") (pinfunction "1_4") (pintype "passive"))
      (node (ref "R54") (pin "2") (pinfunction "2_2") (pintype "passive"))
    )
    (net (code "76") (name "Net-(J10E-1)") (class "Default")
      (node (ref "J10") (pin "5") (pinfunction "1_5") (pintype "passive"))
      (node (ref "R55") (pin "1") (pinfunction "1_1") (pintype "passive"))
    )
    (net (code "77") (name "Net-(J10F-1)") (class "Default")
      (node (ref "J10") (pin "6") (pinfunction "1_6") (pintype "passive"))
      (node (ref "R56") (pin "2") (pinfunction "2_2") (pintype "passive"))
    )
    (net (code "78") (name "Net-(J10G-1)") (class "Default")
      (node (ref "J10") (pin "7") (pinfunction "1_7") (pintype "passive"))
      (node (ref "R57") (pin "1") (pinfunction "1_1") (pintype "passive"))
    )
    (net (code "79") (name "Net-(J10H-1)") (class "Default")
      (node (ref "J10") (pin "8") (pinfunction "1_8") (pintype "passive"))
      (node (ref "R58") (pin "2") (pinfunction "2_2") (pintype "passive"))
    )
    (net (code "80") (name "Net-(J100-3V3-Pad1)") (class "Default")
      (node (ref "J100") (pin "1") (pinfunction "3V3_1") (pintype "power_in"))
      (node (ref "J100") (pin "17") (pinfunction "3V3_17") (pintype "power_in"))
      (node (ref "R16") (pin "1") (pinfunction "1_1") (pintype "passive"))
    )
    (net (code "81") (name "Net-(LCD100-A0)") (class "Default")
      (node (ref "LCD100") (pin "7") (pinfunction "A0_7") (pintype "bidirectional"))
      (node (ref "SJ5") (pin "1") (pinfunction "1_1") (pintype "passive"))
    )
    (net (code "82") (name "Net-(LCD100-LED+)") (class "Default")
      (node (ref "LCD100") (pin "15") (pinfunction "LED+_15") (pintype "bidirectional"))
      (node (ref "R14") (pin "2") (pinfunction "2_2") (pintype "passive"))
    )
    (net (code "83") (name "Net-(LCD100-LED-)") (class "Default")
      (node (ref "LCD100") (pin "16") (pinfunction "LED-_16") (pintype "bidirectional"))
      (node (ref "Q1") (pin "1") (pinfunction "D_1") (pintype "passive"))
    )
    (net (code "84") (name "Net-(LCD100-RESET)") (class "Default")
      (node (ref "LCD100") (pin "6") (pinfunction "RESET_6") (pintype "bidirectional"))
      (node (ref "SJ6") (pin "1") (pinfunction "1_1") (pintype "passive"))
    )
    (net (code "85") (name "Net-(LCD100-TFT_CLK)") (class "Default")
      (node (ref "LCD100") (pin "9") (pinfunction "TFT_CLK_9") (pintype "bidirectional"))
      (node (ref "SJ3") (pin "1") (pinfunction "1_1") (pintype "passive"))
    )
    (net (code "86") (name "Net-(LCD100-TFT_CS)") (class "Default")
      (node (ref "LCD100") (pin "10") (pinfunction "TFT_CS_10") (pintype "bidirectional"))
      (node (ref "SJ2") (pin "1") (pinfunction "1_1") (pintype "passive"))
    )
    (net (code "87") (name "Net-(LCD100-TFT_DAT)") (class "Default")
      (node (ref "LCD100") (pin "8") (pinfunction "TFT_DAT_8") (pintype "bidirectional"))
      (node (ref "SJ4") (pin "1") (pinfunction "1_1") (pintype "passive"))
    )
    (net (code "88") (name "Net-(LED1-PadA)") (class "Default")
      (node (ref "LED1") (pin "A") (pinfunction "A_A") (pintype "passive"))
      (node (ref "R1") (pin "2") (pinfunction "2_2") (pintype "passive"))
    )
    (net (code "89") (name "Net-(LED2-PadA)") (class "Default")
      (node (ref "LED2") (pin "A") (pinfunction "A_A") (pintype "passive"))
      (node (ref "R3") (pin "2") (pinfunction "2_2") (pintype "passive"))
    )
    (net (code "90") (name "Net-(LED3-PadA)") (class "Default")
      (node (ref "LED3") (pin "A") (pinfunction "A_A") (pintype "passive"))
      (node (ref "R7") (pin "2") (pinfunction "2_2") (pintype "passive"))
    )
    (net (code "91") (name "Net-(LED4-PadA)") (class "Default")
      (node (ref "LED4") (pin "A") (pinfunction "A_A") (pintype "passive"))
      (node (ref "R5") (pin "2") (pinfunction "2_2") (pintype "passive"))
    )
    (net (code "92") (name "Net-(LED100-PadA)") (class "Default")
      (node (ref "LED100") (pin "A") (pinfunction "A_A") (pintype "passive"))
      (node (ref "R30") (pin "1") (pinfunction "1_1") (pintype "passive"))
    )
    (net (code "93") (name "Net-(LED101-PadA)") (class "Default")
      (node (ref "LED101") (pin "A") (pinfunction "A_A") (pintype "passive"))
      (node (ref "R29") (pin "1") (pinfunction "1_1") (pintype "passive"))
    )
    (net (code "94") (name "Net-(Q1-G)") (class "Default")
      (node (ref "Q1") (pin "3") (pinfunction "G_3") (pintype "passive"))
      (node (ref "R15") (pin "2") (pinfunction "2_2") (pintype "passive"))
      (node (ref "SJ1") (pin "1") (pinfunction "1_1") (pintype "passive"))
    )
    (net (code "95") (name "OUT0") (class "Default")
      (node (ref "D3") (pin "3") (pinfunction "C1A2_3") (pintype "passive"))
      (node (ref "IC5") (pin "8") (pinfunction "P04_8") (pintype "bidirectional"))
      (node (ref "R45") (pin "1") (pinfunction "1_1") (pintype "passive"))
      (node (ref "R47") (pin "2") (pinfunction "2_2") (pintype "passive"))
    )
    (net (code "96") (name "OUT0P") (class "Default")
      (node (ref "J7") (pin "1") (pinfunction "1_1") (pintype "passive"))
      (node (ref "J9") (pin "1") (pinfunction "1_1") (pintype "bidirectional"))
      (node (ref "R45") (pin "2") (pinfunction "2_2") (pintype "passive"))
    )
    (net (code "97") (name "OUT1") (class "Default")
      (node (ref "D10") (pin "3") (pinfunction "C1A2_3") (pintype "passive"))
      (node (ref "IC5") (pin "9") (pinfunction "P05_9") (pintype "bidirectional"))
      (node (ref "R44") (pin "1") (pinfunction "1_1") (pintype "passive"))
      (node (ref "R48") (pin "2") (pinfunction "2_2") (pintype "passive"))
    )
    (net (code "98") (name "OUT1P") (class "Default")
      (node (ref "J7") (pin "3") (pinfunction "3_3") (pintype "passive"))
      (node (ref "J9") (pin "2") (pinfunction "2_2") (pintype "bidirectional"))
      (node (ref "R44") (pin "2") (pinfunction "2_2") (pintype "passive"))
    )
    (net (code "99") (name "OUT2") (class "Default")
      (node (ref "D8") (pin "3") (pinfunction "C1A2_3") (pintype "passive"))
      (node (ref "IC5") (pin "10") (pinfunction "P06_10") (pintype "bidirectional"))
      (node (ref "R42") (pin "1") (pinfunction "1_1") (pintype "passive"))
      (node (ref "R49") (pin "2") (pinfunction "2_2") (pintype "passive"))
    )
    (net (code "100") (name "OUT2P") (class "Default")
      (node (ref "J6") (pin "1") (pinfunction "1_1") (pintype "bidirectional"))
      (node (ref "J7") (pin "5") (pinfunction "5_5") (pintype "passive"))
      (node (ref "R42") (pin "2") (pinfunction "2_2") (pintype "passive"))
    )
    (net (code "101") (name "OUT3") (class "Default")
      (node (ref "D9") (pin "3") (pinfunction "C1A2_3") (pintype "passive"))
      (node (ref "IC5") (pin "11") (pinfunction "P07_11") (pintype "bidirectional"))
      (node (ref "R41") (pin "1") (pinfunction "1_1") (pintype "passive"))
      (node (ref "R50") (pin "2") (pinfunction "2_2") (pintype "passive"))
    )
    (net (code "102") (name "OUT3P") (class "Default")
      (node (ref "J6") (pin "2") (pinfunction "2_2") (pintype "bidirectional"))
      (node (ref "J7") (pin "7") (pinfunction "7_7") (pintype "passive"))
      (node (ref "R41") (pin "2") (pinfunction "2_2") (pintype "passive"))
    )
    (net (code "103") (name "RFID_RX") (class "Default")
      (node (ref "D2") (pin "3") (pinfunction "C1A2_3") (pintype "passive"))
      (node (ref "J100") (pin "8") (pinfunction "TXD0/GPIO14_8") (pintype "bidirectional"))
      (node (ref "J7") (pin "11") (pinfunction "11_11") (pintype "passive"))
      (node (ref "R24") (pin "1") (pinfunction "1_1") (pintype "passive"))
    )
    (net (code "104") (name "RFID_TX") (class "Default")
      (node (ref "D1") (pin "3") (pinfunction "C1A2_3") (pintype "passive"))
      (node (ref "J100") (pin "10") (pinfunction "RXD0/GPIO15_10") (pintype "bidirectional"))
      (node (ref "J7") (pin "9") (pinfunction "9_9") (pintype "passive"))
      (node (ref "R19") (pin "2") (pinfunction "2_2") (pintype "passive"))
      (node (ref "R21") (pin "1") (pinfunction "1_1") (pintype "passive"))
    )
    (net (code "105") (name "SHUTDOWN") (class "Default")
      (node (ref "IC2") (pin "3") (pinfunction "D1_3") (pintype "input"))
      (node (ref "J100") (pin "13") (pinfunction "GPIO27/GEN2_13") (pintype "bidirectional"))
      (node (ref "R6") (pin "2") (pinfunction "2_2") (pintype "passive"))
    )
    (net (code "106") (name "unconnected-(IC4-BP-Pad4)") (class "Default")
      (node (ref "IC4") (pin "4") (pinfunction "BP_4") (pintype "input"))
    )
    (net (code "107") (name "unconnected-(J100-GEN{slash}6GPIO25-Pad22)") (class "Default")
      (node (ref "J100") (pin "22") (pinfunction "GEN/6GPIO25_22") (pintype "bidirectional"))
    )
    (net (code "108") (name "unconnected-(J100-GPIO6-Pad31)") (class "Default")
      (node (ref "J100") (pin "31") (pinfunction "GPIO6_31") (pintype "bidirectional"))
    )
    (net (code "109") (name "unconnected-(J100-GPIO13-Pad33)") (class "Default")
      (node (ref "J100") (pin "33") (pinfunction "GPIO13_33") (pintype "bidirectional"))
    )
    (net (code "110") (name "unconnected-(J100-GPIO16-Pad36)") (class "Default")
      (node (ref "J100") (pin "36") (pinfunction "GPIO16_36") (pintype "bidirectional"))
    )
    (net (code "111") (name "unconnected-(J100-GPIO20-Pad38)") (class "Default")
      (node (ref "J100") (pin "38") (pinfunction "GPIO20_38") (pintype "bidirectional"))
    )
    (net (code "112") (name "unconnected-(J100-GPIO22{slash}GEN3-Pad15)") (class "Default")
      (node (ref "J100") (pin "15") (pinfunction "GPIO22/GEN3_15") (pintype "bidirectional"))
    )
    (net (code "113") (name "unconnected-(J100-ID_SC-Pad28)") (class "Default")
      (node (ref "J100") (pin "28") (pinfunction "ID_SC_28") (pintype "bidirectional"))
    )
    (net (code "114") (name "unconnected-(J100-ID_SD-Pad27)") (class "Default")
      (node (ref "J100") (pin "27") (pinfunction "ID_SD_27") (pintype "bidirectional"))
    )
    (net (code "115") (name "unconnected-(J100-~{CE}{slash}GPIO7-Pad26)") (class "Default")
      (node (ref "J100") (pin "26") (pinfunction "~{CE}/GPIO7_26") (pintype "bidirectional"))
    )
    (net (code "116") (name "unconnected-(LCD100-NC-Pad3)") (class "Default")
      (node (ref "LCD100") (pin "3") (pinfunction "NC_3") (pintype "bidirectional"))
    )
    (net (code "117") (name "unconnected-(LCD100-NC-Pad4)") (class "Default")
      (node (ref "LCD100") (pin "4") (pinfunction "NC_4") (pintype "bidirectional"))
    )
    (net (code "118") (name "unconnected-(LCD100-NC-Pad5)") (class "Default")
      (node (ref "LCD100") (pin "5") (pinfunction "NC_5") (pintype "bidirectional"))
    )
    (net (code "119") (name "unconnected-(LCD100-SD_CS-Pad14)") (class "Default")
      (node (ref "LCD100") (pin "14") (pinfunction "SD_CS_14") (pintype "bidirectional"))
    )
    (net (code "120") (name "unconnected-(LCD100-SD_MISO-Pad12)") (class "Default")
      (node (ref "LCD100") (pin "12") (pinfunction "SD_MISO_12") (pintype "bidirectional"))
    )
    (net (code "121") (name "unconnected-(LCD100-SD_MOSI-Pad13)") (class "Default")
      (node (ref "LCD100") (pin "13") (pinfunction "SD_MOSI_13") (pintype "bidirectional"))
    )
    (net (code "122") (name "unconnected-(LCD100-SD_SCK-Pad11)") (class "Default")
      (node (ref "LCD100") (pin "11") (pinfunction "SD_SCK_11") (pintype "bidirectional"))
    )
  )
)
